# 1power.net
KiCad netlist of a schematic drawn in Altium Designer
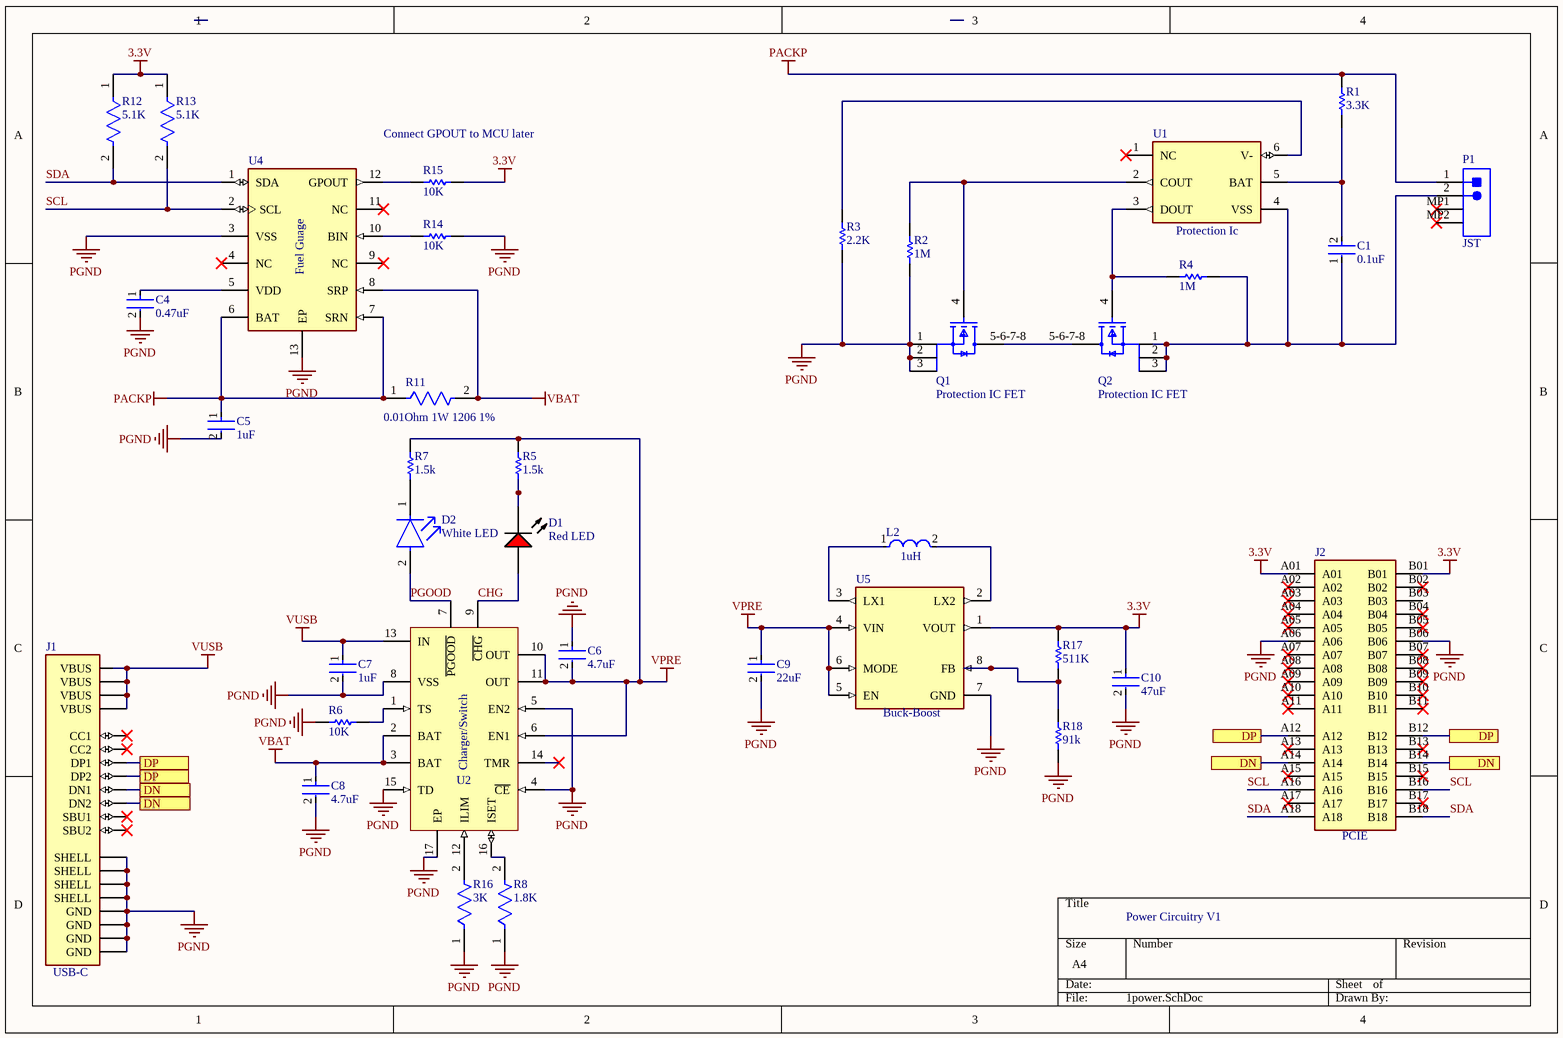
[diagram p0: 1power.SchDoc]

(export (version "E")
  (design (tool "Eeschema 10.0.6"))
  (components
    (comp (ref "C1")
      (value "0.1uF")
      (footprint "FP-GRM15-MFG")
      (description "CAP CER 0.1UF 16V X7R 0402")
      (fields (field (name "MANUFACTURER PART NUMBER") "GRM155R71C104KA88D") (field (name "TOLERANCE") "10%"))
      (libsource (lib "Altium Content Vault") (part "236180d848d6139a670b325ea6854c9"))
    )
    (comp (ref "C4")
      (value "0.47uF")
      (footprint "FP-C0603C-CF-MFG")
      (description "CAP CER 0.47UF 16V X7R 0603")
      (fields (field (name "TOLERANCE") "0.1") (field (name "MANUFACTURER PART NUMBER") "C0603C474K4RACTU"))
      (libsource (lib "Altium Content Vault") (part "b4654b650e69147ec39a6b967a45e02"))
    )
    (comp (ref "C5")
      (value "1uF")
      (footprint "FP-C0402C105K8PACTU-MFG")
      (description "CAP CER 1UF 10V X5R 0402")
      (fields (field (name "VOLTAGE") "10V") (field (name "TOLERANCE") "10%"))
      (libsource (lib "Altium Content Vault") (part "11868f565c42a9108669ba33697ecf6"))
    )
    (comp (ref "C6")
      (value "4.7uF")
      (footprint "FP-ZRB15X-0_15-MFG")
      (description "CAP CER 4.7UF 10V X5R 0402")
      (fields (field (name "TOLERANCE") "20%") (field (name "VOLTAGE") "10V"))
      (libsource (lib "Altium Content Vault") (part "b4654b650e69147ec39a6b967a45e02"))
    )
    (comp (ref "C7")
      (value "1uF")
      (footprint "FP-C0402C105K8PACTU-MFG")
      (description "CAP CER 1UF 10V X5R 0402")
      (fields (field (name "VOLTAGE") "10V") (field (name "TOLERANCE") "10%"))
      (libsource (lib "Altium Content Vault") (part "11868f565c42a9108669ba33697ecf6"))
    )
    (comp (ref "C8")
      (value "4.7uF")
      (footprint "FP-ZRB15X-0_15-MFG")
      (description "CAP CER 4.7UF 10V X5R 0402")
      (fields (field (name "TOLERANCE") "20%") (field (name "VOLTAGE") "10V"))
      (libsource (lib "Altium Content Vault") (part "b4654b650e69147ec39a6b967a45e02"))
    )
    (comp (ref "C9")
      (value "22uF")
      (footprint "FP-GRM187-0_2-IPC_C")
      (description "Chip Multilayer Ceramic Capacitors for General Purpose, 0603, 22uF, X5R, 15%, 20%, 10V")
      (fields (field (name "TOLERANCE") "20%"))
      (libsource (lib "Altium Content Vault") (part "02cd4be3c70576c341d710602a673aa"))
    )
    (comp (ref "C10")
      (value "47uF")
      (footprint "FP-GRM219-0_2-0_1-IPC_A")
      (description "Chip Multilayer Ceramic Capacitors for General Purpose, 0805, 47uF, X5R, 15%, 20%, 6.3V")
      (fields (field (name "TOLERANCE") "20%"))
      (libsource (lib "Altium Content Vault") (part "02cd4be3c70576c341d710602a673aa"))
    )
    (comp (ref "D1")
      (value "Red LED")
      (footprint "VISH-TLMS1000_V")
      (description "Low Current LED, 40 mW, 1.8 V, -40 to 100 degC, 2-Pin SMD (0603), RoHS, Tape and Reel")
      (fields (field (name "MANUFACTURER") "Vishay"))
      (libsource (lib "Altium Content Vault") (part "LED-RED-AK-2"))
    )
    (comp (ref "D2")
      (value "White LED")
      (footprint "FP-6_541-5091_01-4-MFG")
      (description "LED COOL WHITE 0603 SMD")
      (fields
        (field (name "MANUFACTURER") "Vishay")
        (field (name "MANUFACTURER PART NUMBER") "VLMW1300-GS08")
      )
      (libsource (lib "Altium Content Vault") (part "8706943c75ba83719d021d2fdc84c58"))
    )
    (comp (ref "J1")
      (value "USB-C")
      (footprint "GCT_USB4085-GF-A_REVB")
      (fields (field (name "MF") "Global Connector Technology") (field (name "MP") "USB4085-GF-A"))
      (libsource (lib "Schlib1") (part "USB4085-GF-A_REVB"))
    )
    (comp (ref "J2")
      (value "PCIE")
      (footprint "SAMTEC_PCIE-036-02-X-D-EMS3")
      (description "PCI EXPRESS EDGE MOUNT ASSEMBLY,36PINS.")
      (fields (field (name "MP") "PCIE-036-02-X-D-EMS3"))
      (libsource (lib "Schlib1") (part "PCIE-036-02-X-D-EMS3"))
    )
    (comp (ref "L2")
      (value "1uH")
      (footprint "FP-DFE252012C-IPC_B")
      (description "Shielded Wirewound Inductor 1uH 20% 3200mA 0.042Ω 1008 (2520), DFE252012P-1R0M=P2")
      (fields (field (name "TOLERANCE") "20%"))
      (libsource (lib "Altium Content Vault") (part "725321dda6339637d4d059423bc1c3c"))
    )
    (comp (ref "P1")
      (value "JST")
      (footprint "JST- S2B-PH-SM4-TB(LF)(SN)-2_V")
      (description "Male Header, Pitch 2 mm, 1 x 2 Position, Height 5.5 mm, -25 to 85 degC, RoHS, Tape and Reel")
      (libsource (lib "Schlib1") (part "CMP-1755-00001-1"))
    )
    (comp (ref "Q1")
      (value "Protection IC FET")
      (footprint "FP-DQG0008A-MFG")
      (description "Protection IC FET, MOSFET N-CH 25V 60A 8-SON, CSD16406Q3")
      (libsource (lib "Schlib1") (part "CMP-04962-000044-1"))
    )
    (comp (ref "Q2")
      (value "Protection IC FET")
      (footprint "FP-DQG0008A-MFG")
      (description "Protection IC FET, MOSFET N-CH 25V 60A 8-SON, CSD16406Q3")
      (libsource (lib "Schlib1") (part "CMP-04962-000044-1"))
    )
    (comp (ref "R1")
      (value "3.3K")
      (footprint "RESC1005X40X25LL05T10")
      (fields (field (name "MANUFACTURER") "Yageo / Phycomp") (field (name "PART NUMBER") "RC0402FR-073K3L"))
      (libsource (lib "Altium Content Vault") (part "RES"))
    )
    (comp (ref "R2")
      (value "1M")
      (footprint "RESC1005X40X25NL05T10")
      (fields (field (name "MANUFACTURER") "Yageo / Phycomp") (field (name "PART NUMBER") "RC0402FR-071ML"))
      (libsource (lib "Altium Content Vault") (part "RES"))
    )
    (comp (ref "R3")
      (value "2.2K")
      (footprint "RESC1005X40X25NL05T10")
      (fields (field (name "MANUFACTURER") "Yageo / Phycomp") (field (name "PART NUMBER") "RC0402FR-072K2L"))
      (libsource (lib "Altium Content Vault") (part "RES"))
    )
    (comp (ref "R4")
      (value "1M")
      (footprint "RESC1005X40X25NL05T10")
      (fields (field (name "MANUFACTURER") "Yageo / Phycomp") (field (name "PART NUMBER") "RC0402FR-071ML"))
      (libsource (lib "Altium Content Vault") (part "RES"))
    )
    (comp (ref "R5")
      (value "1.5k")
      (footprint "RESC1005X40X25ML05T10")
      (fields (field (name "MANUFACTURER") "Yageo / Phycomp") (field (name "PART NUMBER") "RC0402FR-071K5L"))
      (libsource (lib "Altium Content Vault") (part "RES"))
    )
    (comp (ref "R6")
      (value "10K")
      (footprint "RESC1005X40X25LL05T10")
      (fields (field (name "PART NUMBER") "RC0402FR-0710KL") (field (name "MANUFACTURER") "Yageo / Phycomp"))
      (libsource (lib "Altium Content Vault") (part "RES"))
    )
    (comp (ref "R7")
      (value "1.5k")
      (footprint "RESC1005X40X25ML05T10")
      (fields (field (name "MANUFACTURER") "Yageo / Phycomp") (field (name "PART NUMBER") "RC0402FR-071K5L"))
      (libsource (lib "Altium Content Vault") (part "RES"))
    )
    (comp (ref "R8")
      (value "1.8K")
      (footprint "FP-CRCW0603-e3-IPC_A")
      (description "RES Thick Film, 1.8kΩ, 1%, 0.1W, 100ppm/°C, 0603")
      (fields (field (name "TOLERANCE") "1%"))
      (libsource (lib "Altium Content Vault") (part "1029c3af85768c4190bb7ad29bc67b5"))
    )
    (comp (ref "R11")
      (value "0.01Ohm 1W 1206 1%")
      (footprint "FP-WSLP1206-FP_1_65x1_93x-MFG")
      (description "RES 0.01 OHM 1% 1W 1206")
      (fields (field (name "TOLERANCE") "1%"))
      (libsource (lib "Altium Content Vault") (part "1029c3af85768c4190bb7ad29bc67b5"))
    )
    (comp (ref "R12")
      (value "5.1K")
      (footprint "FP-CRCW0402-e3-IPC_A")
      (description "RES Thick Film, 5.1kΩ, 1%, 0.063W, 100ppm/°C, 0402")
      (fields (field (name "TOLERANCE") "1%"))
      (libsource (lib "Altium Content Vault") (part "1029c3af85768c4190bb7ad29bc67b5"))
    )
    (comp (ref "R13")
      (value "5.1K")
      (footprint "FP-CRCW0402-e3-IPC_A")
      (description "RES Thick Film, 5.1kΩ, 1%, 0.063W, 100ppm/°C, 0402")
      (fields (field (name "TOLERANCE") "1%"))
      (libsource (lib "Altium Content Vault") (part "1029c3af85768c4190bb7ad29bc67b5"))
    )
    (comp (ref "R14")
      (value "10K")
      (footprint "RESC1005X40X25LL05T10")
      (fields (field (name "PART NUMBER") "RC0402FR-0710KL") (field (name "MANUFACTURER") "Yageo / Phycomp"))
      (libsource (lib "Altium Content Vault") (part "RES"))
    )
    (comp (ref "R15")
      (value "10K")
      (footprint "RESC1005X40X25LL05T10")
      (fields (field (name "PART NUMBER") "RC0402FR-0710KL") (field (name "MANUFACTURER") "Yageo / Phycomp"))
      (libsource (lib "Altium Content Vault") (part "RES"))
    )
    (comp (ref "R16")
      (value "3K")
      (footprint "FP-CRCW0603-e3-MFG")
      (description "RES Thick Film, 3kΩ, 1%, 0.1W, 100ppm/°C, 0603")
      (fields (field (name "TOLERANCE") "1%"))
      (libsource (lib "Altium Content Vault") (part "1029c3af85768c4190bb7ad29bc67b5"))
    )
    (comp (ref "R17")
      (value "511K")
      (footprint "RESC1005X40X25ML05T05")
      (fields (field (name "PART NUMBER") "ERJ-2RKF5113X") (field (name "MANUFACTURER") "Panasonic"))
      (libsource (lib "Altium Content Vault") (part "RES"))
    )
    (comp (ref "R18")
      (value "91k")
      (footprint "RESC1005X40X25NL05T10")
      (fields (field (name "MANUFACTURER") "Yageo / Phycomp") (field (name "PART NUMBER") "RC0402FR-0791KL"))
      (libsource (lib "Altium Content Vault") (part "RES"))
    )
    (comp (ref "U1")
      (value "Protection Ic")
      (footprint "FP-DSE0006A-IPC_A")
      (description "Power Supply Support Circuit, Fixed, 1 Channel, PDSO6")
      (fields
        (field (name "MANUFACTURER") "Texas Instruments")
        (field (name "MANUFACTURER PART NUMBER") "BQ29701DSER")
      )
      (libsource (lib "Schlib1") (part "BQ29701DSER"))
    )
    (comp (ref "U2")
      (value "Charger/Switch")
      (footprint "RGT0016C_V")
      (fields (field (name "PARTNUMBER") "BQ24072RGTT") (field (name "MANUFACTURER") "Texas Instruments"))
      (libsource (lib "Altium Content Vault") (part "TI-BQ24072RGT16-1700X1700TP"))
    )
    (comp (ref "U4")
      (value "Fuel Guage")
      (footprint "FP-DRZ0012A-MFG")
      (description "IC BATT FUEL GAUGE LICOO2 12SON")
      (fields
        (field (name "OCTOPART") "https://octopart.com/bq27441drzt-g1a-texas+instruments-30555831")
        (field (name "MANUFACTURER") "Texas Instruments")
      )
      (libsource (lib "Altium Content Vault") (part "c803e035ce0891ae19034f27297cdee"))
    )
    (comp (ref "U5")
      (value "Buck-Boost")
      (footprint "SOT50P160X60-8N")
      (description "1.5-A output current, high-power-density buck-boost converter")
      (fields (field (name "MF") "Texas Instruments") (field (name "MP") "TPS631000DRLR"))
      (libsource (lib "Schlib1") (part "TPS631000DRLR"))
    )
  )
  (nets
    (net (code "1") (name "/CHG") (class "Default")
      (node (ref "D1") (pin "1") (pinfunction "A_1") (pintype "passive"))
      (node (ref "U2") (pin "9") (pinfunction "~{CHG}_9") (pintype "tri_state"))
    )
    (net (code "2") (name "/DN") (class "Default")
      (node (ref "J1") (pin "A7") (pinfunction "DN1_A7") (pintype "bidirectional"))
      (node (ref "J1") (pin "B7") (pinfunction "DN2_B7") (pintype "bidirectional"))
      (node (ref "J2") (pin "A14") (pinfunction "A14_A14") (pintype "passive"))
      (node (ref "J2") (pin "B14") (pinfunction "B14_B14") (pintype "passive"))
    )
    (net (code "3") (name "/DP") (class "Default")
      (node (ref "J1") (pin "A6") (pinfunction "DP1_A6") (pintype "bidirectional"))
      (node (ref "J1") (pin "B6") (pinfunction "DP2_B6") (pintype "bidirectional"))
      (node (ref "J2") (pin "A12") (pinfunction "A12_A12") (pintype "passive"))
      (node (ref "J2") (pin "B12") (pinfunction "B12_B12") (pintype "passive"))
    )
    (net (code "4") (name "/PGOOD") (class "Default")
      (node (ref "D2") (pin "2") (pinfunction "A_2") (pintype "passive"))
      (node (ref "U2") (pin "7") (pinfunction "~{PGOOD}_7") (pintype "tri_state"))
    )
    (net (code "5") (name "/SCL") (class "Default")
      (node (ref "J2") (pin "A16") (pinfunction "A16_A16") (pintype "passive"))
      (node (ref "J2") (pin "B16") (pinfunction "B16_B16") (pintype "passive"))
      (node (ref "R13") (pin "2") (pinfunction "2_2") (pintype "passive"))
      (node (ref "U4") (pin "2") (pinfunction "SCL_2") (pintype "bidirectional"))
    )
    (net (code "6") (name "/SDA") (class "Default")
      (node (ref "J2") (pin "A18") (pinfunction "A18_A18") (pintype "passive"))
      (node (ref "J2") (pin "B18") (pinfunction "B18_B18") (pintype "passive"))
      (node (ref "R12") (pin "2") (pinfunction "2_2") (pintype "passive"))
      (node (ref "U4") (pin "1") (pinfunction "SDA_1") (pintype "bidirectional"))
    )
    (net (code "7") (name "3.3V") (class "Default")
      (node (ref "C10") (pin "1") (pinfunction "1_1") (pintype "passive"))
      (node (ref "J2") (pin "A01") (pinfunction "A01_A01") (pintype "passive"))
      (node (ref "J2") (pin "B01") (pinfunction "B01_B01") (pintype "passive"))
      (node (ref "R12") (pin "1") (pinfunction "1_1") (pintype "passive"))
      (node (ref "R13") (pin "1") (pinfunction "1_1") (pintype "passive"))
      (node (ref "R15") (pin "2") (pinfunction "2_2") (pintype "passive"))
      (node (ref "R17") (pin "2") (pinfunction "2_2") (pintype "passive"))
      (node (ref "U5") (pin "1") (pinfunction "VOUT_1") (pintype "output"))
    )
    (net (code "8") (name "Net-(D1-K)") (class "Default")
      (node (ref "D1") (pin "2") (pinfunction "K_2") (pintype "passive"))
      (node (ref "R5") (pin "1") (pinfunction "1_1") (pintype "passive"))
    )
    (net (code "9") (name "Net-(D2-C)") (class "Default")
      (node (ref "D2") (pin "1") (pinfunction "C_1") (pintype "passive"))
      (node (ref "R7") (pin "1") (pinfunction "1_1") (pintype "passive"))
    )
    (net (code "10") (name "Net-(Q1-D)") (class "Default")
      (node (ref "Q1") (pin "5-6-7-8") (pinfunction "D_5-6-7-8") (pintype "passive"))
      (node (ref "Q2") (pin "5-6-7-8") (pinfunction "D_5-6-7-8") (pintype "passive"))
    )
    (net (code "11") (name "Net-(Q1-G)") (class "Default")
      (node (ref "Q1") (pin "4") (pinfunction "G_4") (pintype "passive"))
      (node (ref "R2") (pin "2") (pinfunction "2_2") (pintype "passive"))
      (node (ref "U1") (pin "2") (pinfunction "COUT_2") (pintype "output"))
    )
    (net (code "12") (name "Net-(Q2-G)") (class "Default")
      (node (ref "Q2") (pin "4") (pinfunction "G_4") (pintype "passive"))
      (node (ref "R4") (pin "1") (pinfunction "1_1") (pintype "passive"))
      (node (ref "U1") (pin "3") (pinfunction "DOUT_3") (pintype "output"))
    )
    (net (code "13") (name "Net-(U1-BAT)") (class "Default")
      (node (ref "C1") (pin "2") (pinfunction "2_2") (pintype "passive"))
      (node (ref "R1") (pin "2") (pinfunction "2_2") (pintype "passive"))
      (node (ref "U1") (pin "5") (pinfunction "BAT_5") (pintype "power_in"))
    )
    (net (code "14") (name "Net-(U1-V-)") (class "Default")
      (node (ref "R3") (pin "2") (pinfunction "2_2") (pintype "passive"))
      (node (ref "U1") (pin "6") (pinfunction "V-_6") (pintype "bidirectional"))
    )
    (net (code "15") (name "Net-(U1-VSS)") (class "Default")
      (node (ref "C1") (pin "1") (pinfunction "1_1") (pintype "passive"))
      (node (ref "P1") (pin "2") (pinfunction "2_2") (pintype "passive"))
      (node (ref "Q2") (pin "1") (pinfunction "S_1") (pintype "passive"))
      (node (ref "Q2") (pin "2") (pinfunction "S_2") (pintype "passive"))
      (node (ref "Q2") (pin "3") (pinfunction "S_3") (pintype "passive"))
      (node (ref "R4") (pin "2") (pinfunction "2_2") (pintype "passive"))
      (node (ref "U1") (pin "4") (pinfunction "VSS_4") (pintype "power_in"))
    )
    (net (code "16") (name "Net-(U2-ILIM)") (class "Default")
      (node (ref "R16") (pin "2") (pinfunction "2_2") (pintype "passive"))
      (node (ref "U2") (pin "12") (pinfunction "ILIM_12") (pintype "input"))
    )
    (net (code "17") (name "Net-(U2-ISET)") (class "Default")
      (node (ref "R8") (pin "2") (pinfunction "2_2") (pintype "passive"))
      (node (ref "U2") (pin "16") (pinfunction "ISET_16") (pintype "bidirectional"))
    )
    (net (code "18") (name "Net-(U2-TS)") (class "Default")
      (node (ref "R6") (pin "2") (pinfunction "2_2") (pintype "passive"))
      (node (ref "U2") (pin "1") (pinfunction "TS_1") (pintype "input"))
    )
    (net (code "19") (name "Net-(U4-BIN)") (class "Default")
      (node (ref "R14") (pin "1") (pinfunction "1_1") (pintype "passive"))
      (node (ref "U4") (pin "10") (pinfunction "BIN_10") (pintype "input"))
    )
    (net (code "20") (name "Net-(U4-GPOUT)") (class "Default")
      (node (ref "R15") (pin "1") (pinfunction "1_1") (pintype "passive"))
      (node (ref "U4") (pin "12") (pinfunction "GPOUT_12") (pintype "output"))
    )
    (net (code "21") (name "Net-(U4-VDD)") (class "Default")
      (node (ref "C4") (pin "1") (pinfunction "1_1") (pintype "passive"))
      (node (ref "U4") (pin "5") (pinfunction "VDD_5") (pintype "power_in"))
    )
    (net (code "22") (name "Net-(U5-FB)") (class "Default")
      (node (ref "R17") (pin "1") (pinfunction "1_1") (pintype "passive"))
      (node (ref "R18") (pin "2") (pinfunction "2_2") (pintype "passive"))
      (node (ref "U5") (pin "8") (pinfunction "FB_8") (pintype "input"))
    )
    (net (code "23") (name "Net-(U5-LX1)") (class "Default")
      (node (ref "L2") (pin "1") (pinfunction "1_1") (pintype "passive"))
      (node (ref "U5") (pin "3") (pinfunction "LX1_3") (pintype "output"))
    )
    (net (code "24") (name "Net-(U5-LX2)") (class "Default")
      (node (ref "L2") (pin "2") (pinfunction "2_2") (pintype "passive"))
      (node (ref "U5") (pin "2") (pinfunction "LX2_2") (pintype "output"))
    )
    (net (code "25") (name "PACKP") (class "Default")
      (node (ref "C5") (pin "1") (pinfunction "1_1") (pintype "passive"))
      (node (ref "P1") (pin "1") (pinfunction "1_1") (pintype "passive"))
      (node (ref "R1") (pin "1") (pinfunction "1_1") (pintype "passive"))
      (node (ref "R11") (pin "1") (pinfunction "1_1") (pintype "passive"))
      (node (ref "U4") (pin "6") (pinfunction "BAT_6") (pintype "power_in"))
      (node (ref "U4") (pin "7") (pinfunction "SRN_7") (pintype "input"))
    )
    (net (code "26") (name "PGND") (class "Default")
      (node (ref "C10") (pin "2") (pinfunction "2_2") (pintype "passive"))
      (node (ref "C4") (pin "2") (pinfunction "2_2") (pintype "passive"))
      (node (ref "C5") (pin "2") (pinfunction "2_2") (pintype "passive"))
      (node (ref "C6") (pin "1") (pinfunction "1_1") (pintype "passive"))
      (node (ref "C7") (pin "2") (pinfunction "2_2") (pintype "passive"))
      (node (ref "C8") (pin "2") (pinfunction "2_2") (pintype "passive"))
      (node (ref "C9") (pin "2") (pinfunction "2_2") (pintype "passive"))
      (node (ref "J1") (pin "A1") (pinfunction "GND_A1") (pintype "power_in"))
      (node (ref "J1") (pin "A12") (pinfunction "GND_A12") (pintype "power_in"))
      (node (ref "J1") (pin "B1") (pinfunction "GND_B1") (pintype "power_in"))
      (node (ref "J1") (pin "B12") (pinfunction "GND_B12") (pintype "power_in"))
      (node (ref "J1") (pin "S1") (pinfunction "SHELL_S1") (pintype "passive"))
      (node (ref "J1") (pin "S2") (pinfunction "SHELL_S2") (pintype "passive"))
      (node (ref "J1") (pin "S3") (pinfunction "SHELL_S3") (pintype "passive"))
      (node (ref "J1") (pin "S4") (pinfunction "SHELL_S4") (pintype "passive"))
      (node (ref "J2") (pin "A06") (pinfunction "A06_A06") (pintype "passive"))
      (node (ref "J2") (pin "B06") (pinfunction "B06_B06") (pintype "passive"))
      (node (ref "Q1") (pin "1") (pinfunction "S_1") (pintype "passive"))
      (node (ref "Q1") (pin "2") (pinfunction "S_2") (pintype "passive"))
      (node (ref "Q1") (pin "3") (pinfunction "S_3") (pintype "passive"))
      (node (ref "R14") (pin "2") (pinfunction "2_2") (pintype "passive"))
      (node (ref "R16") (pin "1") (pinfunction "1_1") (pintype "passive"))
      (node (ref "R18") (pin "1") (pinfunction "1_1") (pintype "passive"))
      (node (ref "R2") (pin "1") (pinfunction "1_1") (pintype "passive"))
      (node (ref "R3") (pin "1") (pinfunction "1_1") (pintype "passive"))
      (node (ref "R6") (pin "1") (pinfunction "1_1") (pintype "passive"))
      (node (ref "R8") (pin "1") (pinfunction "1_1") (pintype "passive"))
      (node (ref "U2") (pin "15") (pinfunction "TD_15") (pintype "input"))
      (node (ref "U2") (pin "17") (pinfunction "EP_17") (pintype "power_in"))
      (node (ref "U2") (pin "4") (pinfunction "~{CE}_4") (pintype "input"))
      (node (ref "U2") (pin "5") (pinfunction "EN2_5") (pintype "input"))
      (node (ref "U2") (pin "8") (pinfunction "VSS_8") (pintype "power_in"))
      (node (ref "U4") (pin "13") (pinfunction "EP_13") (pintype "power_in"))
      (node (ref "U4") (pin "3") (pinfunction "VSS_3") (pintype "power_in"))
      (node (ref "U5") (pin "7") (pinfunction "GND_7") (pintype "power_in"))
    )
    (net (code "27") (name "VBAT") (class "Default")
      (node (ref "C8") (pin "1") (pinfunction "1_1") (pintype "passive"))
      (node (ref "R11") (pin "2") (pinfunction "2_2") (pintype "passive"))
      (node (ref "U2") (pin "2") (pinfunction "BAT_2") (pintype "power_in"))
      (node (ref "U2") (pin "3") (pinfunction "BAT_3") (pintype "power_in"))
      (node (ref "U4") (pin "8") (pinfunction "SRP_8") (pintype "input"))
    )
    (net (code "28") (name "VPRE") (class "Default")
      (node (ref "C6") (pin "2") (pinfunction "2_2") (pintype "passive"))
      (node (ref "C9") (pin "1") (pinfunction "1_1") (pintype "passive"))
      (node (ref "R5") (pin "2") (pinfunction "2_2") (pintype "passive"))
      (node (ref "R7") (pin "2") (pinfunction "2_2") (pintype "passive"))
      (node (ref "U2") (pin "10") (pinfunction "OUT_10") (pintype "power_in"))
      (node (ref "U2") (pin "11") (pinfunction "OUT_11") (pintype "power_in"))
      (node (ref "U2") (pin "6") (pinfunction "EN1_6") (pintype "input"))
      (node (ref "U5") (pin "4") (pinfunction "VIN_4") (pintype "input"))
      (node (ref "U5") (pin "5") (pinfunction "EN_5") (pintype "input"))
      (node (ref "U5") (pin "6") (pinfunction "MODE_6") (pintype "input"))
    )
    (net (code "29") (name "VUSB") (class "Default")
      (node (ref "C7") (pin "1") (pinfunction "1_1") (pintype "passive"))
      (node (ref "J1") (pin "A4") (pinfunction "VBUS_A4") (pintype "power_in"))
      (node (ref "J1") (pin "A9") (pinfunction "VBUS_A9") (pintype "power_in"))
      (node (ref "J1") (pin "B4") (pinfunction "VBUS_B4") (pintype "power_in"))
      (node (ref "J1") (pin "B9") (pinfunction "VBUS_B9") (pintype "power_in"))
      (node (ref "U2") (pin "13") (pinfunction "IN_13") (pintype "power_in"))
    )
    (net (code "30") (name "unconnected-(J1-CC1-PadA5)") (class "Default")
      (node (ref "J1") (pin "A5") (pinfunction "CC1_A5") (pintype "bidirectional+no_connect"))
    )
    (net (code "31") (name "unconnected-(J1-CC2-PadB5)") (class "Default")
      (node (ref "J1") (pin "B5") (pinfunction "CC2_B5") (pintype "bidirectional+no_connect"))
    )
    (net (code "32") (name "unconnected-(J1-SBU1-PadA8)") (class "Default")
      (node (ref "J1") (pin "A8") (pinfunction "SBU1_A8") (pintype "bidirectional+no_connect"))
    )
    (net (code "33") (name "unconnected-(J1-SBU2-PadB8)") (class "Default")
      (node (ref "J1") (pin "B8") (pinfunction "SBU2_B8") (pintype "bidirectional+no_connect"))
    )
    (net (code "34") (name "unconnected-(J2-PadA02)") (class "Default")
      (node (ref "J2") (pin "A02") (pinfunction "A02_A02") (pintype "passive+no_connect"))
    )
    (net (code "35") (name "unconnected-(J2-PadA03)") (class "Default")
      (node (ref "J2") (pin "A03") (pinfunction "A03_A03") (pintype "passive+no_connect"))
    )
    (net (code "36") (name "unconnected-(J2-PadA04)") (class "Default")
      (node (ref "J2") (pin "A04") (pinfunction "A04_A04") (pintype "passive+no_connect"))
    )
    (net (code "37") (name "unconnected-(J2-PadA05)") (class "Default")
      (node (ref "J2") (pin "A05") (pinfunction "A05_A05") (pintype "passive+no_connect"))
    )
    (net (code "38") (name "unconnected-(J2-PadA07)") (class "Default")
      (node (ref "J2") (pin "A07") (pinfunction "A07_A07") (pintype "passive+no_connect"))
    )
    (net (code "39") (name "unconnected-(J2-PadA08)") (class "Default")
      (node (ref "J2") (pin "A08") (pinfunction "A08_A08") (pintype "passive+no_connect"))
    )
    (net (code "40") (name "unconnected-(J2-PadA09)") (class "Default")
      (node (ref "J2") (pin "A09") (pinfunction "A09_A09") (pintype "passive+no_connect"))
    )
    (net (code "41") (name "unconnected-(J2-PadA10)") (class "Default")
      (node (ref "J2") (pin "A10") (pinfunction "A10_A10") (pintype "passive+no_connect"))
    )
    (net (code "42") (name "unconnected-(J2-PadA11)") (class "Default")
      (node (ref "J2") (pin "A11") (pinfunction "A11_A11") (pintype "passive+no_connect"))
    )
    (net (code "43") (name "unconnected-(J2-PadA13)") (class "Default")
      (node (ref "J2") (pin "A13") (pinfunction "A13_A13") (pintype "passive+no_connect"))
    )
    (net (code "44") (name "unconnected-(J2-PadA15)") (class "Default")
      (node (ref "J2") (pin "A15") (pinfunction "A15_A15") (pintype "passive+no_connect"))
    )
    (net (code "45") (name "unconnected-(J2-PadA17)") (class "Default")
      (node (ref "J2") (pin "A17") (pinfunction "A17_A17") (pintype "passive+no_connect"))
    )
    (net (code "46") (name "unconnected-(J2-PadB02)") (class "Default")
      (node (ref "J2") (pin "B02") (pinfunction "B02_B02") (pintype "passive+no_connect"))
    )
    (net (code "47") (name "unconnected-(J2-PadB03)") (class "Default")
      (node (ref "J2") (pin "B03") (pinfunction "B03_B03") (pintype "passive"))
    )
    (net (code "48") (name "unconnected-(J2-PadB04)") (class "Default")
      (node (ref "J2") (pin "B04") (pinfunction "B04_B04") (pintype "passive+no_connect"))
    )
    (net (code "49") (name "unconnected-(J2-PadB05)") (class "Default")
      (node (ref "J2") (pin "B05") (pinfunction "B05_B05") (pintype "passive+no_connect"))
    )
    (net (code "50") (name "unconnected-(J2-PadB07)") (class "Default")
      (node (ref "J2") (pin "B07") (pinfunction "B07_B07") (pintype "passive+no_connect"))
    )
    (net (code "51") (name "unconnected-(J2-PadB08)") (class "Default")
      (node (ref "J2") (pin "B08") (pinfunction "B08_B08") (pintype "passive+no_connect"))
    )
    (net (code "52") (name "unconnected-(J2-PadB09)") (class "Default")
      (node (ref "J2") (pin "B09") (pinfunction "B09_B09") (pintype "passive+no_connect"))
    )
    (net (code "53") (name "unconnected-(J2-PadB10)") (class "Default")
      (node (ref "J2") (pin "B10") (pinfunction "B10_B10") (pintype "passive+no_connect"))
    )
    (net (code "54") (name "unconnected-(J2-PadB11)") (class "Default")
      (node (ref "J2") (pin "B11") (pinfunction "B11_B11") (pintype "passive+no_connect"))
    )
    (net (code "55") (name "unconnected-(J2-PadB13)") (class "Default")
      (node (ref "J2") (pin "B13") (pinfunction "B13_B13") (pintype "passive+no_connect"))
    )
    (net (code "56") (name "unconnected-(J2-PadB15)") (class "Default")
      (node (ref "J2") (pin "B15") (pinfunction "B15_B15") (pintype "passive+no_connect"))
    )
    (net (code "57") (name "unconnected-(J2-PadB17)") (class "Default")
      (node (ref "J2") (pin "B17") (pinfunction "B17_B17") (pintype "passive+no_connect"))
    )
    (net (code "58") (name "unconnected-(P1-PadMP1)") (class "Default")
      (node (ref "P1") (pin "MP1") (pinfunction "MP1_MP1") (pintype "passive+no_connect"))
    )
    (net (code "59") (name "unconnected-(P1-PadMP2)") (class "Default")
      (node (ref "P1") (pin "MP2") (pinfunction "MP2_MP2") (pintype "passive+no_connect"))
    )
    (net (code "60") (name "unconnected-(U1-NC-Pad1)") (class "Default")
      (node (ref "U1") (pin "1") (pinfunction "NC_1") (pintype "passive+no_connect"))
    )
    (net (code "61") (name "unconnected-(U2-TMR-Pad14)") (class "Default")
      (node (ref "U2") (pin "14") (pinfunction "TMR_14") (pintype "passive+no_connect"))
    )
    (net (code "62") (name "unconnected-(U4-NC-Pad4)") (class "Default")
      (node (ref "U4") (pin "4") (pinfunction "NC_4") (pintype "passive+no_connect"))
    )
    (net (code "63") (name "unconnected-(U4-NC-Pad9)") (class "Default")
      (node (ref "U4") (pin "9") (pinfunction "NC_9") (pintype "power_in+no_connect"))
    )
    (net (code "64") (name "unconnected-(U4-NC-Pad11)") (class "Default")
      (node (ref "U4") (pin "11") (pinfunction "NC_11") (pintype "passive+no_connect"))
    )
  )
)
